# Charlotte5822_32-Channel-Wireless-Headst.net
KiCad netlist of a schematic drawn in Altium Designer
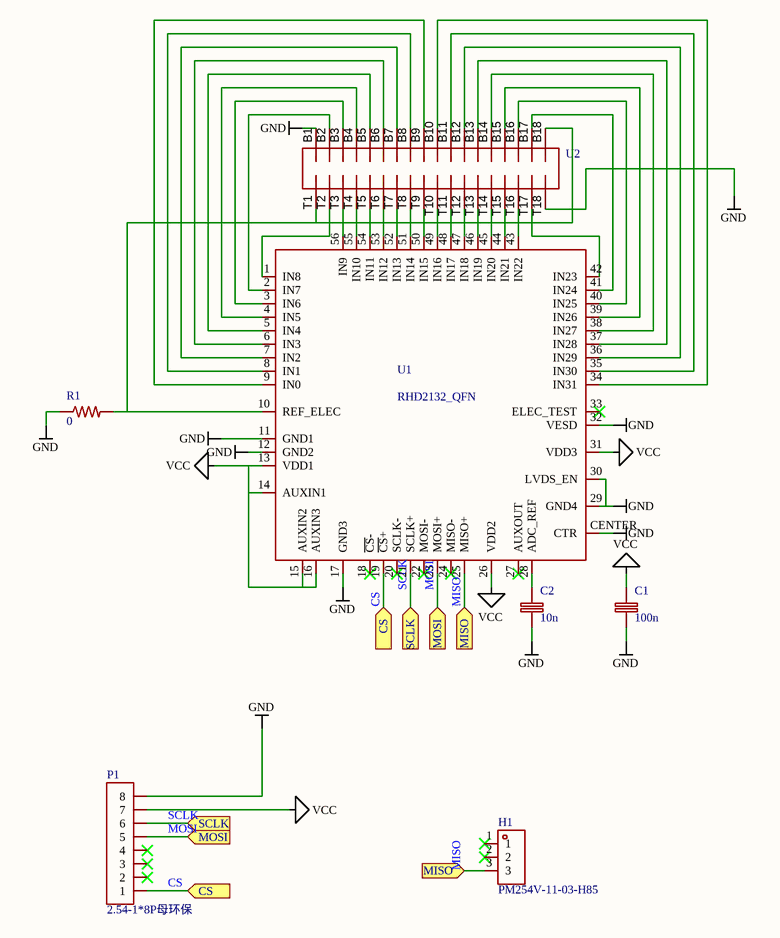
[diagram p0: Charlotte5822_32-Channel-Wireless-Headstage__PCB_AltiumDesigner_IntanRHD2132_Schematic1__1_P1.schdoc]

(export (version "E")
  (design (tool "Eeschema 10.0.6"))
  (components
    (comp (ref "C1")
      (value "100n")
      (libsource (lib "altium-import") (part "root_0_RHD2000_eval_board_C__0402_"))
    )
    (comp (ref "C2")
      (value "10n")
      (libsource (lib "altium-import") (part "root_0_RHD2000_eval_board_C__0402_"))
    )
    (comp (ref "H1")
      (value "PM254V-11-03-H85")
      (description "插孔结构:1x3P;间距:2.54mm;行距:-;安装类型:直插;排数:单排;总孔位数:3P;塑高:-;触头材质:黄铜;触头镀层:-;")
      (fields (field (name "MANUFACTURER") "XFCN(兴飞)"))
      (libsource (lib "altium-import") (part "root_0_PM254V-11-03-H85_"))
    )
    (comp (ref "P1")
      (value "2.54-1*8P母环保")
      (description "插孔结构:1x8P;间距:2.54mm;行距:-;安装类型:直插;排数:单排;总孔位数:8P;塑高:-;触头材质:-;触头镀层:-;")
      (fields (field (name "MANUFACTURER") "BOOMELE(博穆精密)"))
      (libsource (lib "altium-import") (part "root_2_2.54-1*8P母环保_"))
    )
    (comp (ref "R1")
      (value "0")
      (libsource (lib "altium-import") (part "root_0_RHD2000_eval_board_R__0402_"))
    )
    (comp (ref "U1")
      (value "RHD2132_QFN")
      (libsource (lib "altium-import") (part "root_0_RHD2000_RHD2132__QFN_"))
    )
    (comp (ref "U2")
      (value "OMNETICS_A79027")
      (libsource (lib "altium-import") (part "root_1_OMNETICS_A79027_"))
    )
  )
  (nets
    (net (code "1") (name "/CS") (class "Default")
      (node (ref "P1") (pin "1") (pinfunction "1_1") (pintype "passive"))
      (node (ref "U1") (pin "19") (pinfunction "~{CS}+_19") (pintype "passive"))
    )
    (net (code "2") (name "/MISO") (class "Default")
      (node (ref "H1") (pin "3") (pinfunction "3_3") (pintype "passive"))
      (node (ref "U1") (pin "25") (pinfunction "MISO+_25") (pintype "passive"))
    )
    (net (code "3") (name "/MOSI") (class "Default")
      (node (ref "P1") (pin "5") (pinfunction "5_5") (pintype "passive"))
      (node (ref "U1") (pin "23") (pinfunction "MOSI+_23") (pintype "passive"))
    )
    (net (code "4") (name "/SCLK") (class "Default")
      (node (ref "P1") (pin "6") (pinfunction "6_6") (pintype "passive"))
      (node (ref "U1") (pin "21") (pinfunction "SCLK+_21") (pintype "passive"))
    )
    (net (code "5") (name "GND") (class "Default")
      (node (ref "C1") (pin "2") (pinfunction "2_2") (pintype "passive"))
      (node (ref "C2") (pin "2") (pinfunction "2_2") (pintype "passive"))
      (node (ref "P1") (pin "8") (pinfunction "8_8") (pintype "passive"))
      (node (ref "R1") (pin "1") (pinfunction "1_1") (pintype "passive"))
      (node (ref "U1") (pin "11") (pinfunction "GND1_11") (pintype "passive"))
      (node (ref "U1") (pin "12") (pinfunction "GND2_12") (pintype "passive"))
      (node (ref "U1") (pin "17") (pinfunction "GND3_17") (pintype "passive"))
      (node (ref "U1") (pin "29") (pinfunction "GND4_29") (pintype "passive"))
      (node (ref "U1") (pin "30") (pinfunction "LVDS_EN_30") (pintype "passive"))
      (node (ref "U1") (pin "32") (pinfunction "VESD_32") (pintype "passive"))
      (node (ref "U1") (pin "CENTER") (pinfunction "CTR_CENTER") (pintype "passive"))
      (node (ref "U2") (pin "B1") (pinfunction "B1_B1") (pintype "passive"))
      (node (ref "U2") (pin "T18") (pinfunction "T18_T18") (pintype "passive"))
    )
    (net (code "6") (name "Net-(U1-ADC_REF)") (class "Default")
      (node (ref "C2") (pin "1") (pinfunction "1_1") (pintype "passive"))
      (node (ref "U1") (pin "28") (pinfunction "ADC_REF_28") (pintype "passive"))
    )
    (net (code "7") (name "Net-(U1-IN0)") (class "Default")
      (node (ref "U1") (pin "9") (pinfunction "IN0_9") (pintype "passive"))
      (node (ref "U2") (pin "B9") (pinfunction "B9_B9") (pintype "passive"))
    )
    (net (code "8") (name "Net-(U1-IN1)") (class "Default")
      (node (ref "U1") (pin "8") (pinfunction "IN1_8") (pintype "passive"))
      (node (ref "U2") (pin "B8") (pinfunction "B8_B8") (pintype "passive"))
    )
    (net (code "9") (name "Net-(U1-IN2)") (class "Default")
      (node (ref "U1") (pin "7") (pinfunction "IN2_7") (pintype "passive"))
      (node (ref "U2") (pin "B7") (pinfunction "B7_B7") (pintype "passive"))
    )
    (net (code "10") (name "Net-(U1-IN3)") (class "Default")
      (node (ref "U1") (pin "6") (pinfunction "IN3_6") (pintype "passive"))
      (node (ref "U2") (pin "B6") (pinfunction "B6_B6") (pintype "passive"))
    )
    (net (code "11") (name "Net-(U1-IN4)") (class "Default")
      (node (ref "U1") (pin "5") (pinfunction "IN4_5") (pintype "passive"))
      (node (ref "U2") (pin "B5") (pinfunction "B5_B5") (pintype "passive"))
    )
    (net (code "12") (name "Net-(U1-IN5)") (class "Default")
      (node (ref "U1") (pin "4") (pinfunction "IN5_4") (pintype "passive"))
      (node (ref "U2") (pin "B4") (pinfunction "B4_B4") (pintype "passive"))
    )
    (net (code "13") (name "Net-(U1-IN6)") (class "Default")
      (node (ref "U1") (pin "3") (pinfunction "IN6_3") (pintype "passive"))
      (node (ref "U2") (pin "B3") (pinfunction "B3_B3") (pintype "passive"))
    )
    (net (code "14") (name "Net-(U1-IN7)") (class "Default")
      (node (ref "U1") (pin "2") (pinfunction "IN7_2") (pintype "passive"))
      (node (ref "U2") (pin "B2") (pinfunction "B2_B2") (pintype "passive"))
    )
    (net (code "15") (name "Net-(U1-IN8)") (class "Default")
      (node (ref "U1") (pin "1") (pinfunction "IN8_1") (pintype "passive"))
      (node (ref "U2") (pin "T2") (pinfunction "T2_T2") (pintype "passive"))
    )
    (net (code "16") (name "Net-(U1-IN9)") (class "Default")
      (node (ref "U1") (pin "56") (pinfunction "IN9_56") (pintype "passive"))
      (node (ref "U2") (pin "T3") (pinfunction "T3_T3") (pintype "passive"))
    )
    (net (code "17") (name "Net-(U1-IN10)") (class "Default")
      (node (ref "U1") (pin "55") (pinfunction "IN10_55") (pintype "passive"))
      (node (ref "U2") (pin "T4") (pinfunction "T4_T4") (pintype "passive"))
    )
    (net (code "18") (name "Net-(U1-IN11)") (class "Default")
      (node (ref "U1") (pin "54") (pinfunction "IN11_54") (pintype "passive"))
      (node (ref "U2") (pin "T5") (pinfunction "T5_T5") (pintype "passive"))
    )
    (net (code "19") (name "Net-(U1-IN12)") (class "Default")
      (node (ref "U1") (pin "53") (pinfunction "IN12_53") (pintype "passive"))
      (node (ref "U2") (pin "T6") (pinfunction "T6_T6") (pintype "passive"))
    )
    (net (code "20") (name "Net-(U1-IN13)") (class "Default")
      (node (ref "U1") (pin "52") (pinfunction "IN13_52") (pintype "passive"))
      (node (ref "U2") (pin "T7") (pinfunction "T7_T7") (pintype "passive"))
    )
    (net (code "21") (name "Net-(U1-IN14)") (class "Default")
      (node (ref "U1") (pin "51") (pinfunction "IN14_51") (pintype "passive"))
      (node (ref "U2") (pin "T8") (pinfunction "T8_T8") (pintype "passive"))
    )
    (net (code "22") (name "Net-(U1-IN15)") (class "Default")
      (node (ref "U1") (pin "50") (pinfunction "IN15_50") (pintype "passive"))
      (node (ref "U2") (pin "T9") (pinfunction "T9_T9") (pintype "passive"))
    )
    (net (code "23") (name "Net-(U1-IN16)") (class "Default")
      (node (ref "U1") (pin "49") (pinfunction "IN16_49") (pintype "passive"))
      (node (ref "U2") (pin "T10") (pinfunction "T10_T10") (pintype "passive"))
    )
    (net (code "24") (name "Net-(U1-IN17)") (class "Default")
      (node (ref "U1") (pin "48") (pinfunction "IN17_48") (pintype "passive"))
      (node (ref "U2") (pin "T11") (pinfunction "T11_T11") (pintype "passive"))
    )
    (net (code "25") (name "Net-(U1-IN18)") (class "Default")
      (node (ref "U1") (pin "47") (pinfunction "IN18_47") (pintype "passive"))
      (node (ref "U2") (pin "T12") (pinfunction "T12_T12") (pintype "passive"))
    )
    (net (code "26") (name "Net-(U1-IN19)") (class "Default")
      (node (ref "U1") (pin "46") (pinfunction "IN19_46") (pintype "passive"))
      (node (ref "U2") (pin "T13") (pinfunction "T13_T13") (pintype "passive"))
    )
    (net (code "27") (name "Net-(U1-IN20)") (class "Default")
      (node (ref "U1") (pin "45") (pinfunction "IN20_45") (pintype "passive"))
      (node (ref "U2") (pin "T14") (pinfunction "T14_T14") (pintype "passive"))
    )
    (net (code "28") (name "Net-(U1-IN21)") (class "Default")
      (node (ref "U1") (pin "44") (pinfunction "IN21_44") (pintype "passive"))
      (node (ref "U2") (pin "T15") (pinfunction "T15_T15") (pintype "passive"))
    )
    (net (code "29") (name "Net-(U1-IN22)") (class "Default")
      (node (ref "U1") (pin "43") (pinfunction "IN22_43") (pintype "passive"))
      (node (ref "U2") (pin "T16") (pinfunction "T16_T16") (pintype "passive"))
    )
    (net (code "30") (name "Net-(U1-IN23)") (class "Default")
      (node (ref "U1") (pin "42") (pinfunction "IN23_42") (pintype "passive"))
      (node (ref "U2") (pin "T17") (pinfunction "T17_T17") (pintype "passive"))
    )
    (net (code "31") (name "Net-(U1-IN24)") (class "Default")
      (node (ref "U1") (pin "41") (pinfunction "IN24_41") (pintype "passive"))
      (node (ref "U2") (pin "B17") (pinfunction "B17_B17") (pintype "passive"))
    )
    (net (code "32") (name "Net-(U1-IN25)") (class "Default")
      (node (ref "U1") (pin "40") (pinfunction "IN25_40") (pintype "passive"))
      (node (ref "U2") (pin "B16") (pinfunction "B16_B16") (pintype "passive"))
    )
    (net (code "33") (name "Net-(U1-IN26)") (class "Default")
      (node (ref "U1") (pin "39") (pinfunction "IN26_39") (pintype "passive"))
      (node (ref "U2") (pin "B15") (pinfunction "B15_B15") (pintype "passive"))
    )
    (net (code "34") (name "Net-(U1-IN27)") (class "Default")
      (node (ref "U1") (pin "38") (pinfunction "IN27_38") (pintype "passive"))
      (node (ref "U2") (pin "B14") (pinfunction "B14_B14") (pintype "passive"))
    )
    (net (code "35") (name "Net-(U1-IN28)") (class "Default")
      (node (ref "U1") (pin "37") (pinfunction "IN28_37") (pintype "passive"))
      (node (ref "U2") (pin "B13") (pinfunction "B13_B13") (pintype "passive"))
    )
    (net (code "36") (name "Net-(U1-IN29)") (class "Default")
      (node (ref "U1") (pin "36") (pinfunction "IN29_36") (pintype "passive"))
      (node (ref "U2") (pin "B12") (pinfunction "B12_B12") (pintype "passive"))
    )
    (net (code "37") (name "Net-(U1-IN30)") (class "Default")
      (node (ref "U1") (pin "35") (pinfunction "IN30_35") (pintype "passive"))
      (node (ref "U2") (pin "B11") (pinfunction "B11_B11") (pintype "passive"))
    )
    (net (code "38") (name "Net-(U1-IN31)") (class "Default")
      (node (ref "U1") (pin "34") (pinfunction "IN31_34") (pintype "passive"))
      (node (ref "U2") (pin "B10") (pinfunction "B10_B10") (pintype "passive"))
    )
    (net (code "39") (name "Net-(U1-REF_ELEC)") (class "Default")
      (node (ref "R1") (pin "2") (pinfunction "2_2") (pintype "passive"))
      (node (ref "U1") (pin "10") (pinfunction "REF_ELEC_10") (pintype "passive"))
      (node (ref "U2") (pin "B18") (pinfunction "B18_B18") (pintype "passive"))
      (node (ref "U2") (pin "T1") (pinfunction "T1_T1") (pintype "passive"))
    )
    (net (code "40") (name "VCC") (class "Default")
      (node (ref "C1") (pin "1") (pinfunction "1_1") (pintype "passive"))
      (node (ref "P1") (pin "7") (pinfunction "7_7") (pintype "passive"))
      (node (ref "U1") (pin "13") (pinfunction "VDD1_13") (pintype "passive"))
      (node (ref "U1") (pin "14") (pinfunction "AUXIN1_14") (pintype "passive"))
      (node (ref "U1") (pin "15") (pinfunction "AUXIN2_15") (pintype "passive"))
      (node (ref "U1") (pin "16") (pinfunction "AUXIN3_16") (pintype "passive"))
      (node (ref "U1") (pin "26") (pinfunction "VDD2_26") (pintype "passive"))
      (node (ref "U1") (pin "31") (pinfunction "VDD3_31") (pintype "passive"))
    )
    (net (code "41") (name "unconnected-(H1-Pad1)") (class "Default")
      (node (ref "H1") (pin "1") (pinfunction "1_1") (pintype "passive+no_connect"))
    )
    (net (code "42") (name "unconnected-(H1-Pad2)") (class "Default")
      (node (ref "H1") (pin "2") (pinfunction "2_2") (pintype "passive+no_connect"))
    )
    (net (code "43") (name "unconnected-(P1-Pad2)") (class "Default")
      (node (ref "P1") (pin "2") (pinfunction "2_2") (pintype "passive+no_connect"))
    )
    (net (code "44") (name "unconnected-(P1-Pad3)") (class "Default")
      (node (ref "P1") (pin "3") (pinfunction "3_3") (pintype "passive+no_connect"))
    )
    (net (code "45") (name "unconnected-(P1-Pad4)") (class "Default")
      (node (ref "P1") (pin "4") (pinfunction "4_4") (pintype "passive+no_connect"))
    )
    (net (code "46") (name "unconnected-(U1-AUXOUT-Pad27)") (class "Default")
      (node (ref "U1") (pin "27") (pinfunction "AUXOUT_27") (pintype "passive+no_connect"))
    )
    (net (code "47") (name "unconnected-(U1-ELEC_TEST-Pad33)") (class "Default")
      (node (ref "U1") (pin "33") (pinfunction "ELEC_TEST_33") (pintype "passive+no_connect"))
    )
    (net (code "48") (name "unconnected-(U1-MISO--Pad24)") (class "Default")
      (node (ref "U1") (pin "24") (pinfunction "MISO-_24") (pintype "passive+no_connect"))
    )
    (net (code "49") (name "unconnected-(U1-MOSI--Pad22)") (class "Default")
      (node (ref "U1") (pin "22") (pinfunction "MOSI-_22") (pintype "passive+no_connect"))
    )
    (net (code "50") (name "unconnected-(U1-SCLK--Pad20)") (class "Default")
      (node (ref "U1") (pin "20") (pinfunction "SCLK-_20") (pintype "passive+no_connect"))
    )
    (net (code "51") (name "unconnected-(U1-~{CS}--Pad18)") (class "Default")
      (node (ref "U1") (pin "18") (pinfunction "~{CS}-_18") (pintype "passive+no_connect"))
    )
  )
)
